# qec_pcb_v3.net
KiCad netlist of a schematic drawn in EAGLE
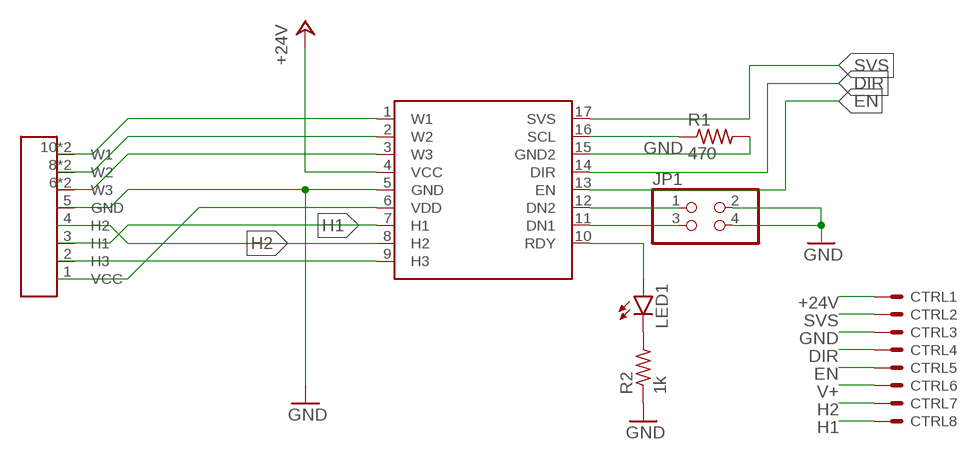
[diagram p0: schematic, sheet 1]

(export (version "E")
  (design (tool "Eeschema 10.0.6"))
  (components
    (comp (ref "CTRL")
      (value "JST8")
      (footprint "eagle-import:JST")
      (libsource (lib "eagle-import") (part "JST8"))
    )
    (comp (ref "JP1")
      (value "PINHD-2X2")
      (footprint "eagle-import:2X02")
      (libsource (lib "eagle-import") (part "PINHD-2X2"))
    )
    (comp (ref "K1")
      (value "68611114122")
      (footprint "eagle-import:68611114122")
      (libsource (lib "eagle-import") (part "68611114122"))
    )
    (comp (ref "LED1")
      (value "LEDCHIPLED_0805")
      (footprint "eagle-import:CHIPLED_0805")
      (libsource (lib "eagle-import") (part "LEDCHIPLED_0805"))
    )
    (comp (ref "R1")
      (value "470")
      (footprint "eagle-import:M0805")
      (libsource (lib "eagle-import") (part "R-US_M0805"))
    )
    (comp (ref "R2")
      (value "1k")
      (footprint "eagle-import:M0805")
      (libsource (lib "eagle-import") (part "R-US_M0805"))
    )
    (comp (ref "U$1")
      (value "1-Q-EC1-Q-EC-SMD")
      (footprint "eagle-import:1-Q-EC-SMD")
      (libsource (lib "eagle-import") (part "1-Q-EC1-Q-EC-SMD"))
    )
  )
  (nets
    (net (code "1") (name "+24V") (class "Default")
      (node (ref "CTRL") (pin "1") (pinfunction "S_1") (pintype "passive"))
      (node (ref "U$1") (pin "4") (pinfunction "VCC_4") (pintype "bidirectional"))
    )
    (net (code "2") (name "/V+") (class "Default")
      (node (ref "CTRL") (pin "6") (pinfunction "S_6") (pintype "passive"))
      (node (ref "K1") (pin "1") (pinfunction "VCC_1") (pintype "bidirectional"))
      (node (ref "U$1") (pin "6") (pinfunction "VDD_6") (pintype "bidirectional"))
    )
    (net (code "3") (name "DIR") (class "Default")
      (node (ref "CTRL") (pin "4") (pinfunction "S_4") (pintype "passive"))
      (node (ref "U$1") (pin "14") (pinfunction "DIR_14") (pintype "bidirectional"))
    )
    (net (code "4") (name "EN") (class "Default")
      (node (ref "CTRL") (pin "5") (pinfunction "S_5") (pintype "passive"))
      (node (ref "U$1") (pin "13") (pinfunction "EN_13") (pintype "bidirectional"))
    )
    (net (code "5") (name "GND") (class "Default")
      (node (ref "CTRL") (pin "3") (pinfunction "S_3") (pintype "passive"))
      (node (ref "JP1") (pin "2") (pinfunction "2_2") (pintype "passive"))
      (node (ref "JP1") (pin "4") (pinfunction "4_4") (pintype "passive"))
      (node (ref "K1") (pin "5") (pinfunction "GND_5") (pintype "bidirectional"))
      (node (ref "R1") (pin "2") (pinfunction "2_2") (pintype "passive"))
      (node (ref "R2") (pin "1") (pinfunction "1_1") (pintype "passive"))
      (node (ref "U$1") (pin "15") (pinfunction "GND2_15") (pintype "bidirectional"))
      (node (ref "U$1") (pin "5") (pinfunction "GND_5") (pintype "bidirectional"))
    )
    (net (code "6") (name "H1") (class "Default")
      (node (ref "CTRL") (pin "8") (pinfunction "S_8") (pintype "passive"))
      (node (ref "K1") (pin "3") (pinfunction "H1_3") (pintype "bidirectional"))
      (node (ref "U$1") (pin "7") (pinfunction "H1_7") (pintype "bidirectional"))
    )
    (net (code "7") (name "H2") (class "Default")
      (node (ref "CTRL") (pin "7") (pinfunction "S_7") (pintype "passive"))
      (node (ref "K1") (pin "4") (pinfunction "H2_4") (pintype "bidirectional"))
      (node (ref "U$1") (pin "8") (pinfunction "H2_8") (pintype "bidirectional"))
    )
    (net (code "8") (name "Net-(K1-H3)") (class "Default")
      (node (ref "K1") (pin "2") (pinfunction "H3_2") (pintype "bidirectional"))
      (node (ref "U$1") (pin "9") (pinfunction "H3_9") (pintype "bidirectional"))
    )
    (net (code "9") (name "Net-(LED1-PadC)") (class "Default")
      (node (ref "LED1") (pin "C") (pinfunction "C_C") (pintype "passive"))
      (node (ref "R2") (pin "2") (pinfunction "2_2") (pintype "passive"))
    )
    (net (code "10") (name "Net-(U$1-DN1)") (class "Default")
      (node (ref "JP1") (pin "3") (pinfunction "3_3") (pintype "passive"))
      (node (ref "U$1") (pin "11") (pinfunction "DN1_11") (pintype "bidirectional"))
    )
    (net (code "11") (name "Net-(U$1-DN2)") (class "Default")
      (node (ref "JP1") (pin "1") (pinfunction "1_1") (pintype "passive"))
      (node (ref "U$1") (pin "12") (pinfunction "DN2_12") (pintype "bidirectional"))
    )
    (net (code "12") (name "Net-(U$1-RDY)") (class "Default")
      (node (ref "LED1") (pin "A") (pinfunction "A_A") (pintype "passive"))
      (node (ref "U$1") (pin "10") (pinfunction "RDY_10") (pintype "bidirectional"))
    )
    (net (code "13") (name "Net-(U$1-SCL)") (class "Default")
      (node (ref "R1") (pin "1") (pinfunction "1_1") (pintype "passive"))
      (node (ref "U$1") (pin "16") (pinfunction "SCL_16") (pintype "bidirectional"))
    )
    (net (code "14") (name "Net-(U$1-W1)") (class "Default")
      (node (ref "K1") (pin "10") (pinfunction "W1_10") (pintype "bidirectional"))
      (node (ref "K1") (pin "11") (pinfunction "W1_11") (pintype "bidirectional"))
      (node (ref "U$1") (pin "1") (pinfunction "W1_1") (pintype "bidirectional"))
    )
    (net (code "15") (name "Net-(U$1-W2)") (class "Default")
      (node (ref "K1") (pin "8") (pinfunction "W2_8") (pintype "bidirectional"))
      (node (ref "K1") (pin "9") (pinfunction "W2_9") (pintype "bidirectional"))
      (node (ref "U$1") (pin "2") (pinfunction "W2_2") (pintype "bidirectional"))
    )
    (net (code "16") (name "Net-(U$1-W3)") (class "Default")
      (node (ref "K1") (pin "6") (pinfunction "W3_6") (pintype "bidirectional"))
      (node (ref "K1") (pin "7") (pinfunction "W3_7") (pintype "bidirectional"))
      (node (ref "U$1") (pin "3") (pinfunction "W3_3") (pintype "bidirectional"))
    )
    (net (code "17") (name "SVS") (class "Default")
      (node (ref "CTRL") (pin "2") (pinfunction "S_2") (pintype "passive"))
      (node (ref "U$1") (pin "17") (pinfunction "SVS_17") (pintype "bidirectional"))
    )
  )
)
